# rapidshark-motor-contor-fault-display-mk.net
KiCad netlist of a schematic drawn in EAGLE
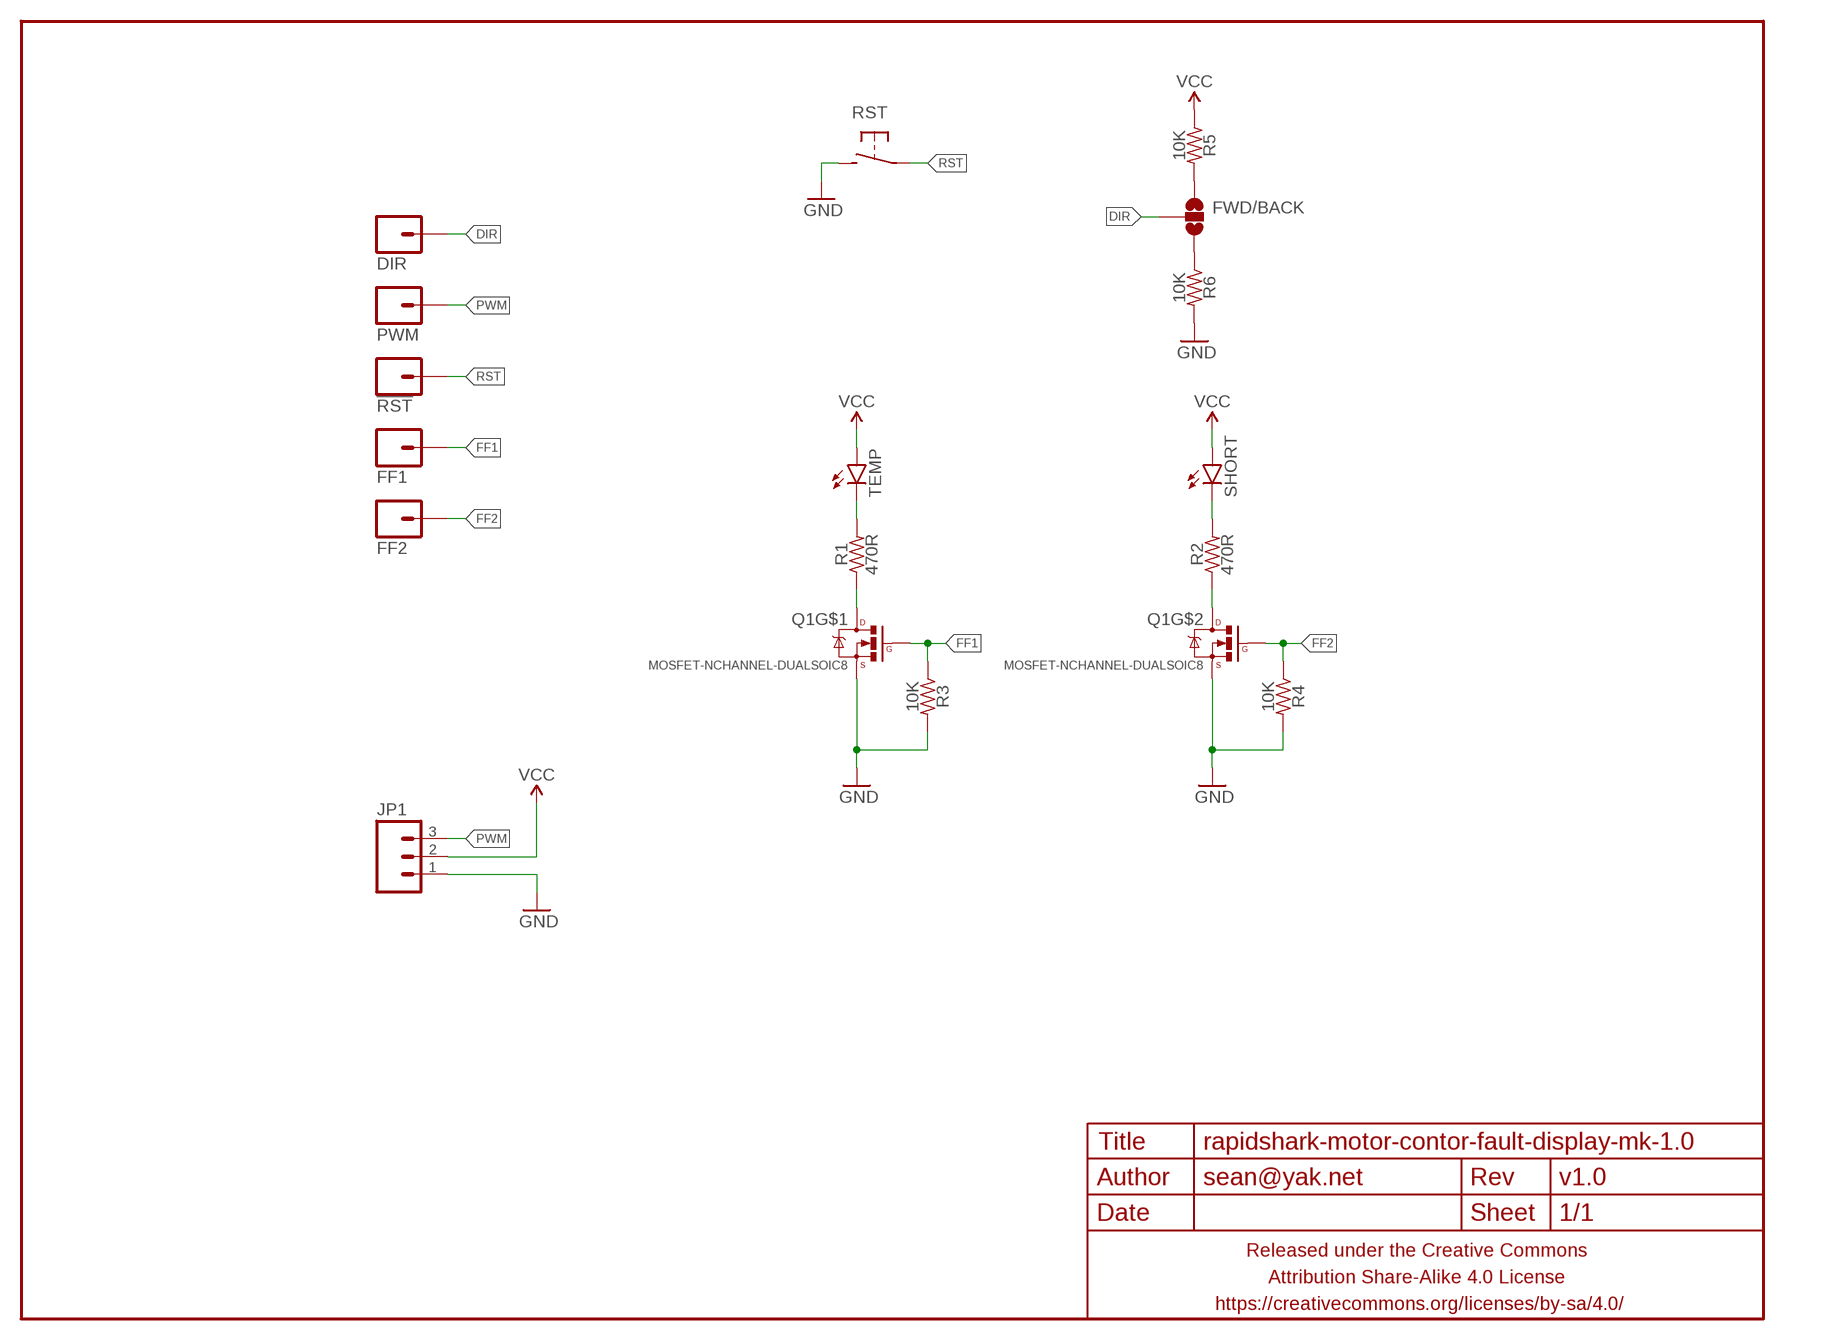
[diagram p0: schematic, sheet 1]

(export (version "E")
  (design (tool "Eeschema 10.0.6"))
  (components
    (comp (ref "!RST")
      (value "M01PTH")
      (footprint "eagle-import:1X01")
      (libsource (lib "eagle-import") (part "M01PTH"))
    )
    (comp (ref "DIR")
      (value "M01PTH")
      (footprint "eagle-import:1X01")
      (libsource (lib "eagle-import") (part "M01PTH"))
    )
    (comp (ref "FF1")
      (value "M01PTH")
      (footprint "eagle-import:1X01")
      (libsource (lib "eagle-import") (part "M01PTH"))
    )
    (comp (ref "FF2")
      (value "M01PTH")
      (footprint "eagle-import:1X01")
      (libsource (lib "eagle-import") (part "M01PTH"))
    )
    (comp (ref "FRAME1")
      (value "FRAME-LETTERNO_PACKAGE")
      (footprint "eagle-import:DUMMY")
      (fields (field (name "DESIGNER") "sean@yak.net") (field (name "VERSION") "v1.0"))
      (libsource (lib "eagle-import") (part "FRAME-LETTERNO_PACKAGE"))
    )
    (comp (ref "FWD/BACK")
      (value "JUMPER-PAD-3-NOFULL_BOX_SILK")
      (footprint "eagle-import:PAD-JUMPER-3-NO_YES_SILK_FULL_BOX")
      (libsource (lib "eagle-import") (part "JUMPER-PAD-3-NOFULL_BOX_SILK"))
    )
    (comp (ref "JP1")
      (value "M03PTH-CENTERED")
      (footprint "eagle-import:1X03-CENTERED")
      (libsource (lib "eagle-import") (part "M03PTH-CENTERED"))
    )
    (comp (ref "PWM")
      (value "M01PTH")
      (footprint "eagle-import:1X01")
      (libsource (lib "eagle-import") (part "M01PTH"))
    )
    (comp (ref "Q1")
      (value "MOSFET-NCHANNEL-DUALSOIC8")
      (footprint "eagle-import:SO08")
      (libsource (lib "eagle-import") (part "MOSFET-NCHANNEL-DUALSOIC8"))
    )
    (comp (ref "R1")
      (value "470R")
      (footprint "eagle-import:R0603-TIGHTER")
      (libsource (lib "eagle-import") (part "RESISTORR0603-TIGHTER"))
    )
    (comp (ref "R2")
      (value "470R")
      (footprint "eagle-import:R0603-TIGHTER")
      (libsource (lib "eagle-import") (part "RESISTORR0603-TIGHTER"))
    )
    (comp (ref "R3")
      (value "10K")
      (footprint "eagle-import:R0603-TIGHTER")
      (libsource (lib "eagle-import") (part "RESISTORR0603-TIGHTER"))
    )
    (comp (ref "R4")
      (value "10K")
      (footprint "eagle-import:R0603-TIGHTER")
      (libsource (lib "eagle-import") (part "RESISTORR0603-TIGHTER"))
    )
    (comp (ref "R5")
      (value "10K")
      (footprint "eagle-import:R0603-TIGHTER")
      (libsource (lib "eagle-import") (part "RESISTORR0603-TIGHTER"))
    )
    (comp (ref "R6")
      (value "10K")
      (footprint "eagle-import:R0603-TIGHTER")
      (libsource (lib "eagle-import") (part "RESISTORR0603-TIGHTER"))
    )
    (comp (ref "RST")
      (value "SPST-NO-TACTCK-PTS840-GK")
      (footprint "eagle-import:TACTILE-SMD-CK-PTS840-GK")
      (libsource (lib "eagle-import") (part "SPST-NO-TACTCK-PTS840-GK"))
    )
    (comp (ref "SHORT")
      (value "LED0603-TIGHT")
      (footprint "eagle-import:LED-0603-TIGHT")
      (libsource (lib "eagle-import") (part "LED0603-TIGHT"))
    )
    (comp (ref "TEMP")
      (value "LED0603-TIGHT")
      (footprint "eagle-import:LED-0603-TIGHT")
      (libsource (lib "eagle-import") (part "LED0603-TIGHT"))
    )
  )
  (nets
    (net (code "1") (name "DIR") (class "Default")
      (node (ref "DIR") (pin "1") (pinfunction "1_1") (pintype "passive"))
      (node (ref "FWD/BACK") (pin "2") (pinfunction "2_2") (pintype "passive"))
    )
    (net (code "2") (name "FF1") (class "Default")
      (node (ref "FF1") (pin "1") (pinfunction "1_1") (pintype "passive"))
      (node (ref "Q1") (pin "2") (pinfunction "G_2") (pintype "passive"))
      (node (ref "R3") (pin "1") (pinfunction "1_1") (pintype "passive"))
    )
    (net (code "3") (name "FF2") (class "Default")
      (node (ref "FF2") (pin "1") (pinfunction "1_1") (pintype "passive"))
      (node (ref "Q1") (pin "4") (pinfunction "G_4") (pintype "passive"))
      (node (ref "R4") (pin "1") (pinfunction "1_1") (pintype "passive"))
    )
    (net (code "4") (name "GND") (class "Default")
      (node (ref "JP1") (pin "1") (pinfunction "1_1") (pintype "passive"))
      (node (ref "Q1") (pin "1") (pinfunction "S_1") (pintype "passive"))
      (node (ref "Q1") (pin "3") (pinfunction "S_3") (pintype "passive"))
      (node (ref "R3") (pin "2") (pinfunction "2_2") (pintype "passive"))
      (node (ref "R4") (pin "2") (pinfunction "2_2") (pintype "passive"))
      (node (ref "R6") (pin "2") (pinfunction "2_2") (pintype "passive"))
      (node (ref "RST") (pin "3") (pinfunction "2_3") (pintype "passive"))
      (node (ref "RST") (pin "4") (pinfunction "2_4") (pintype "passive"))
    )
    (net (code "5") (name "Net-(FWD/BACK-Pad1)") (class "Default")
      (node (ref "FWD/BACK") (pin "1") (pinfunction "1_1") (pintype "passive"))
      (node (ref "R5") (pin "2") (pinfunction "2_2") (pintype "passive"))
    )
    (net (code "6") (name "Net-(FWD/BACK-Pad3)") (class "Default")
      (node (ref "FWD/BACK") (pin "3") (pinfunction "3_3") (pintype "passive"))
      (node (ref "R6") (pin "1") (pinfunction "1_1") (pintype "passive"))
    )
    (net (code "7") (name "Net-(Q1A-D-Pad7)") (class "Default")
      (node (ref "Q1") (pin "7") (pinfunction "D_7") (pintype "passive"))
      (node (ref "Q1") (pin "8") (pinfunction "D_8") (pintype "passive"))
      (node (ref "R1") (pin "1") (pinfunction "1_1") (pintype "passive"))
    )
    (net (code "8") (name "Net-(Q1B-D-Pad5)") (class "Default")
      (node (ref "Q1") (pin "5") (pinfunction "D_5") (pintype "passive"))
      (node (ref "Q1") (pin "6") (pinfunction "D_6") (pintype "passive"))
      (node (ref "R2") (pin "1") (pinfunction "1_1") (pintype "passive"))
    )
    (net (code "9") (name "Net-(R1-Pad2)") (class "Default")
      (node (ref "R1") (pin "2") (pinfunction "2_2") (pintype "passive"))
      (node (ref "TEMP") (pin "C") (pinfunction "C_C") (pintype "passive"))
    )
    (net (code "10") (name "Net-(R2-Pad2)") (class "Default")
      (node (ref "R2") (pin "2") (pinfunction "2_2") (pintype "passive"))
      (node (ref "SHORT") (pin "C") (pinfunction "C_C") (pintype "passive"))
    )
    (net (code "11") (name "PWM") (class "Default")
      (node (ref "JP1") (pin "3") (pinfunction "3_3") (pintype "passive"))
      (node (ref "PWM") (pin "1") (pinfunction "1_1") (pintype "passive"))
    )
    (net (code "12") (name "RST") (class "Default")
      (node (ref "!RST") (pin "1") (pinfunction "1_1") (pintype "passive"))
      (node (ref "RST") (pin "1") (pinfunction "1_1") (pintype "passive"))
      (node (ref "RST") (pin "2") (pinfunction "1_2") (pintype "passive"))
    )
    (net (code "13") (name "VCC") (class "Default")
      (node (ref "JP1") (pin "2") (pinfunction "2_2") (pintype "passive"))
      (node (ref "R5") (pin "1") (pinfunction "1_1") (pintype "passive"))
      (node (ref "SHORT") (pin "A") (pinfunction "A_A") (pintype "passive"))
      (node (ref "TEMP") (pin "A") (pinfunction "A_A") (pintype "passive"))
    )
  )
)
